# EMS_esp32_wifi_v2_4_eagle_v7.net
KiCad netlist of a schematic drawn in EAGLE
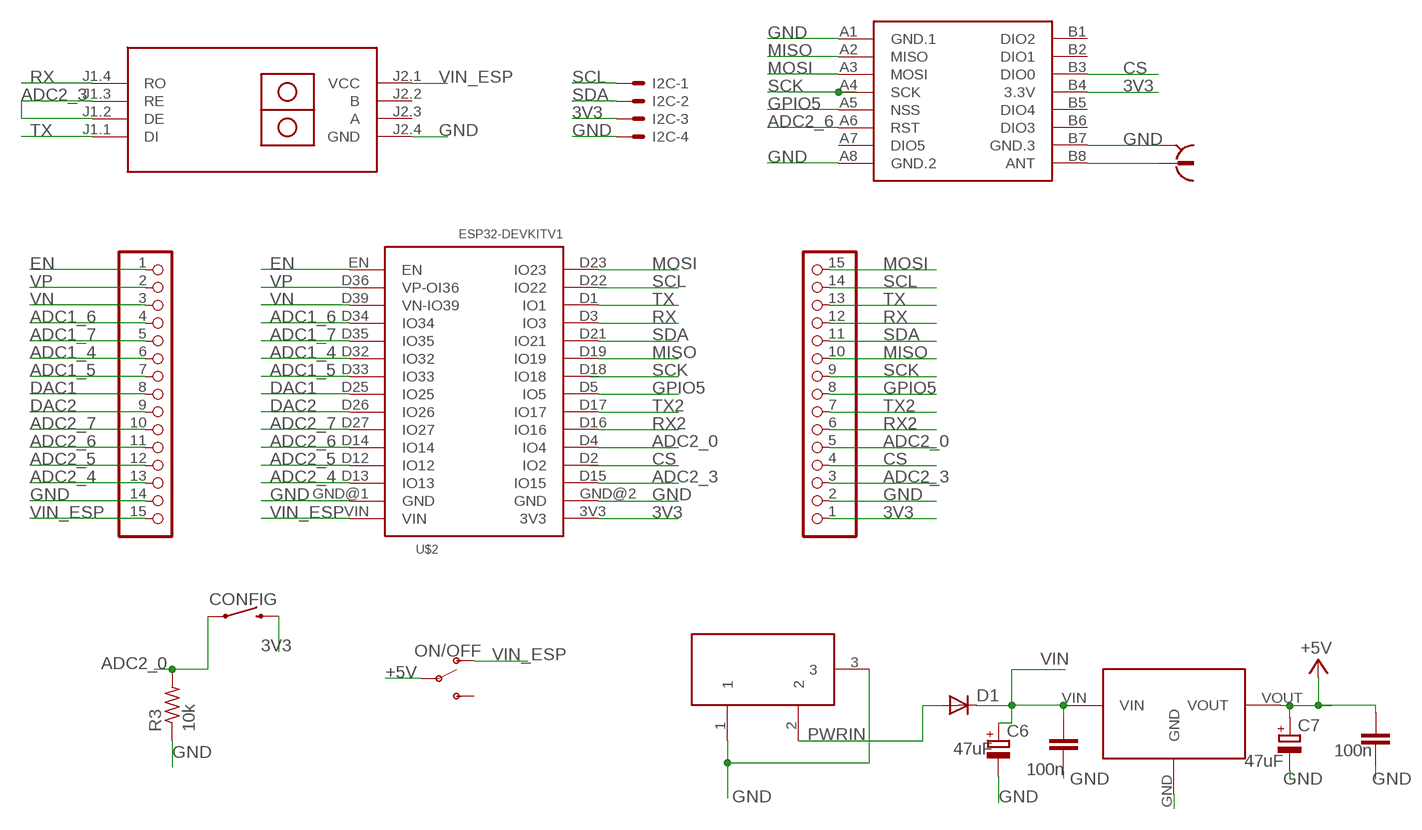
[diagram p0: schematic, sheet 1]

(export (version "E")
  (design (tool "Eeschema 10.0.6"))
  (components
    (comp (ref "C5")
      (value "100n")
      (footprint "eagle-import:C1206")
      (libsource (lib "eagle-import") (part "C-EUC1206"))
    )
    (comp (ref "C6")
      (value "47uF")
      (footprint "eagle-import:PANASONIC_D")
      (libsource (lib "eagle-import") (part "CPOL-EUD"))
    )
    (comp (ref "C7")
      (value "47uF")
      (footprint "eagle-import:PANASONIC_D")
      (libsource (lib "eagle-import") (part "CPOL-EUD"))
    )
    (comp (ref "C14")
      (value "100n")
      (footprint "eagle-import:C1206")
      (libsource (lib "eagle-import") (part "C-EUC1206"))
    )
    (comp (ref "CONFIG")
      (value "MOMENTARY-SWITCH-SPST-PTH-6.0MM")
      (footprint "eagle-import:TACTILE_SWITCH_PTH_6.0MM")
      (libsource (lib "eagle-import") (part "MOMENTARY-SWITCH-SPST-PTH-6.0MM"))
    )
    (comp (ref "D1")
      (value "DIODE-SMB")
      (footprint "eagle-import:SMB")
      (libsource (lib "eagle-import") (part "DIODE-SMB"))
    )
    (comp (ref "I2C")
      (value "22-23-2041")
      (footprint "eagle-import:22-23-2041")
      (fields (field (name "MF") "MOLEX"))
      (libsource (lib "eagle-import") (part "22-23-2041"))
    )
    (comp (ref "JP1")
      (value "PINHD-1X15")
      (footprint "eagle-import:1X15")
      (libsource (lib "eagle-import") (part "PINHD-1X15"))
    )
    (comp (ref "JP2")
      (value "PINHD-1X15")
      (footprint "eagle-import:1X15")
      (libsource (lib "eagle-import") (part "PINHD-1X15"))
    )
    (comp (ref "ON/OFF")
      (value "SWITCH-SPDT-PTH-11.6X4.0MM")
      (footprint "eagle-import:SWITCH_SPDT_PTH_11.6X4.0MM")
      (libsource (lib "eagle-import") (part "SWITCH-SPDT-PTH-11.6X4.0MM"))
    )
    (comp (ref "R3")
      (value "10k")
      (footprint "eagle-import:0204_7")
      (libsource (lib "eagle-import") (part "R-US_0204/7"))
    )
    (comp (ref "RFM95")
      (value "WIRELESS-LORA-RFM95W#SMD")
      (footprint "eagle-import:WIRELESS-LORA-RFM95W#SMD")
      (libsource (lib "eagle-import") (part "WIRELESS-LORA-RFM95W#SMD"))
    )
    (comp (ref "U$1")
      (value "RS485-TTL-CONVERTER")
      (footprint "eagle-import:RS485-TTL-CONVERTER")
      (libsource (lib "eagle-import") (part "RS485-TTL-CONVERTER"))
    )
    (comp (ref "U$2")
      (value "ESP32DEVKITV1")
      (footprint "eagle-import:ESP32-DEVKITV1")
      (libsource (lib "eagle-import") (part "ESP32DEVKITV1"))
    )
    (comp (ref "U$3")
      (value "SMARTPRJ_POWERSUPPLY_DC21MMX")
      (footprint "eagle-import:SMARTPRJ_POWERSUPPLY_DC-21MM")
      (libsource (lib "eagle-import") (part "SMARTPRJ_POWERSUPPLY_DC21MMX"))
    )
    (comp (ref "U$4")
      (value "7805-TO263_7805")
      (footprint "eagle-import:7805-TO263_TO263")
      (libsource (lib "eagle-import") (part "7805-TO263_7805"))
    )
    (comp (ref "X1")
      (value "734120110")
      (footprint "eagle-import:734120110")
      (libsource (lib "eagle-import") (part "734120110"))
    )
  )
  (nets
    (net (code "1") (name "+5V") (class "Default")
      (node (ref "C14") (pin "2") (pinfunction "2_2") (pintype "passive"))
      (node (ref "C7") (pin "+") (pinfunction "+_+") (pintype "passive"))
      (node (ref "ON/OFF") (pin "2") (pinfunction "P_2") (pintype "passive"))
      (node (ref "U$4") (pin "VOUT") (pinfunction "VOUT_VOUT") (pintype "bidirectional"))
    )
    (net (code "2") (name "/3V3") (class "Default")
      (node (ref "CONFIG") (pin "3") (pinfunction "2_3") (pintype "passive"))
      (node (ref "I2C") (pin "3") (pinfunction "S_3") (pintype "passive"))
      (node (ref "JP2") (pin "1") (pinfunction "1_1") (pintype "passive"))
      (node (ref "RFM95") (pin "B4") (pinfunction "3.3V_B4") (pintype "power_in"))
      (node (ref "U$2") (pin "3V3") (pinfunction "3V3_3V3") (pintype "bidirectional"))
    )
    (net (code "3") (name "/ADC1_4") (class "Default")
      (node (ref "JP1") (pin "6") (pinfunction "6_6") (pintype "passive"))
      (node (ref "U$2") (pin "D32") (pinfunction "IO32_D32") (pintype "bidirectional"))
    )
    (net (code "4") (name "/ADC1_5") (class "Default")
      (node (ref "JP1") (pin "7") (pinfunction "7_7") (pintype "passive"))
      (node (ref "U$2") (pin "D33") (pinfunction "IO33_D33") (pintype "bidirectional"))
    )
    (net (code "5") (name "/ADC1_6") (class "Default")
      (node (ref "JP1") (pin "4") (pinfunction "4_4") (pintype "passive"))
      (node (ref "U$2") (pin "D34") (pinfunction "IO34_D34") (pintype "bidirectional"))
    )
    (net (code "6") (name "/ADC1_7") (class "Default")
      (node (ref "JP1") (pin "5") (pinfunction "5_5") (pintype "passive"))
      (node (ref "U$2") (pin "D35") (pinfunction "IO35_D35") (pintype "bidirectional"))
    )
    (net (code "7") (name "/ADC2_0") (class "Default")
      (node (ref "CONFIG") (pin "1") (pinfunction "1_1") (pintype "passive"))
      (node (ref "JP2") (pin "5") (pinfunction "5_5") (pintype "passive"))
      (node (ref "R3") (pin "2") (pinfunction "2_2") (pintype "passive"))
      (node (ref "U$2") (pin "D4") (pinfunction "IO4_D4") (pintype "bidirectional"))
    )
    (net (code "8") (name "/ADC2_3") (class "Default")
      (node (ref "JP2") (pin "3") (pinfunction "3_3") (pintype "passive"))
      (node (ref "U$1") (pin "J1.2") (pinfunction "DE_J1.2") (pintype "passive"))
      (node (ref "U$1") (pin "J1.3") (pinfunction "RE_J1.3") (pintype "passive"))
      (node (ref "U$2") (pin "D15") (pinfunction "IO15_D15") (pintype "bidirectional"))
    )
    (net (code "9") (name "/ADC2_4") (class "Default")
      (node (ref "JP1") (pin "13") (pinfunction "13_13") (pintype "passive"))
      (node (ref "U$2") (pin "D13") (pinfunction "IO13_D13") (pintype "bidirectional"))
    )
    (net (code "10") (name "/ADC2_5") (class "Default")
      (node (ref "JP1") (pin "12") (pinfunction "12_12") (pintype "passive"))
      (node (ref "U$2") (pin "D12") (pinfunction "IO12_D12") (pintype "bidirectional"))
    )
    (net (code "11") (name "/ADC2_6") (class "Default")
      (node (ref "JP1") (pin "11") (pinfunction "11_11") (pintype "passive"))
      (node (ref "RFM95") (pin "A6") (pinfunction "RST_A6") (pintype "bidirectional"))
      (node (ref "U$2") (pin "D14") (pinfunction "IO14_D14") (pintype "bidirectional"))
    )
    (net (code "12") (name "/ADC2_7") (class "Default")
      (node (ref "JP1") (pin "10") (pinfunction "10_10") (pintype "passive"))
      (node (ref "U$2") (pin "D27") (pinfunction "IO27_D27") (pintype "bidirectional"))
    )
    (net (code "13") (name "/CS") (class "Default")
      (node (ref "JP2") (pin "4") (pinfunction "4_4") (pintype "passive"))
      (node (ref "RFM95") (pin "B3") (pinfunction "DIO0_B3") (pintype "bidirectional"))
      (node (ref "U$2") (pin "D2") (pinfunction "IO2_D2") (pintype "bidirectional"))
    )
    (net (code "14") (name "/DAC1") (class "Default")
      (node (ref "JP1") (pin "8") (pinfunction "8_8") (pintype "passive"))
      (node (ref "U$2") (pin "D25") (pinfunction "IO25_D25") (pintype "bidirectional"))
    )
    (net (code "15") (name "/DAC2") (class "Default")
      (node (ref "JP1") (pin "9") (pinfunction "9_9") (pintype "passive"))
      (node (ref "U$2") (pin "D26") (pinfunction "IO26_D26") (pintype "bidirectional"))
    )
    (net (code "16") (name "/EN") (class "Default")
      (node (ref "JP1") (pin "1") (pinfunction "1_1") (pintype "passive"))
      (node (ref "U$2") (pin "EN") (pinfunction "EN_EN") (pintype "bidirectional"))
    )
    (net (code "17") (name "/GND") (class "Default")
      (node (ref "C14") (pin "1") (pinfunction "1_1") (pintype "passive"))
      (node (ref "C5") (pin "1") (pinfunction "1_1") (pintype "passive"))
      (node (ref "C6") (pin "-") (pinfunction "-_-") (pintype "passive"))
      (node (ref "C7") (pin "-") (pinfunction "-_-") (pintype "passive"))
      (node (ref "I2C") (pin "4") (pinfunction "S_4") (pintype "passive"))
      (node (ref "JP1") (pin "14") (pinfunction "14_14") (pintype "passive"))
      (node (ref "JP2") (pin "2") (pinfunction "2_2") (pintype "passive"))
      (node (ref "R3") (pin "1") (pinfunction "1_1") (pintype "passive"))
      (node (ref "RFM95") (pin "A1") (pinfunction "GND.1_A1") (pintype "power_in"))
      (node (ref "RFM95") (pin "A8") (pinfunction "GND.2_A8") (pintype "power_in"))
      (node (ref "RFM95") (pin "B7") (pinfunction "GND.3_B7") (pintype "power_in"))
      (node (ref "U$1") (pin "J2.4") (pinfunction "GND_J2.4") (pintype "power_in"))
      (node (ref "U$2") (pin "GND@1") (pinfunction "GND_GND@1") (pintype "bidirectional"))
      (node (ref "U$2") (pin "GND@2") (pinfunction "GND_GND@2") (pintype "bidirectional"))
      (node (ref "U$3") (pin "1") (pinfunction "1_1") (pintype "power_in"))
      (node (ref "U$3") (pin "3") (pinfunction "3_3") (pintype "power_in"))
      (node (ref "U$4") (pin "GND") (pinfunction "GND_GND") (pintype "bidirectional"))
      (node (ref "X1") (pin "S@1") (pinfunction "2_S@1") (pintype "passive"))
      (node (ref "X1") (pin "S@2") (pinfunction "2_S@2") (pintype "passive"))
      (node (ref "X1") (pin "S@3") (pinfunction "2_S@3") (pintype "passive"))
    )
    (net (code "18") (name "/GPIO5") (class "Default")
      (node (ref "JP2") (pin "8") (pinfunction "8_8") (pintype "passive"))
      (node (ref "RFM95") (pin "A5") (pinfunction "NSS_A5") (pintype "bidirectional"))
      (node (ref "U$2") (pin "D5") (pinfunction "IO5_D5") (pintype "bidirectional"))
    )
    (net (code "19") (name "/MISO") (class "Default")
      (node (ref "JP2") (pin "10") (pinfunction "10_10") (pintype "passive"))
      (node (ref "RFM95") (pin "A2") (pinfunction "MISO_A2") (pintype "bidirectional"))
      (node (ref "U$2") (pin "D19") (pinfunction "IO19_D19") (pintype "bidirectional"))
    )
    (net (code "20") (name "/MOSI") (class "Default")
      (node (ref "JP2") (pin "15") (pinfunction "15_15") (pintype "passive"))
      (node (ref "RFM95") (pin "A3") (pinfunction "MOSI_A3") (pintype "bidirectional"))
      (node (ref "U$2") (pin "D23") (pinfunction "IO23_D23") (pintype "bidirectional"))
    )
    (net (code "21") (name "/PWRIN") (class "Default")
      (node (ref "D1") (pin "A") (pinfunction "A_A") (pintype "passive"))
      (node (ref "U$3") (pin "2") (pinfunction "2_2") (pintype "power_in"))
    )
    (net (code "22") (name "/RX") (class "Default")
      (node (ref "JP2") (pin "12") (pinfunction "12_12") (pintype "passive"))
      (node (ref "U$1") (pin "J1.4") (pinfunction "RO_J1.4") (pintype "passive"))
      (node (ref "U$2") (pin "D3") (pinfunction "IO3_D3") (pintype "bidirectional"))
    )
    (net (code "23") (name "/RX2") (class "Default")
      (node (ref "JP2") (pin "6") (pinfunction "6_6") (pintype "passive"))
      (node (ref "U$2") (pin "D16") (pinfunction "IO16_D16") (pintype "bidirectional"))
    )
    (net (code "24") (name "/SCK") (class "Default")
      (node (ref "JP2") (pin "9") (pinfunction "9_9") (pintype "passive"))
      (node (ref "RFM95") (pin "A4") (pinfunction "SCK_A4") (pintype "bidirectional"))
      (node (ref "U$2") (pin "D18") (pinfunction "IO18_D18") (pintype "bidirectional"))
    )
    (net (code "25") (name "/SCL") (class "Default")
      (node (ref "I2C") (pin "1") (pinfunction "S_1") (pintype "passive"))
      (node (ref "JP2") (pin "14") (pinfunction "14_14") (pintype "passive"))
      (node (ref "U$2") (pin "D22") (pinfunction "IO22_D22") (pintype "bidirectional"))
    )
    (net (code "26") (name "/SDA") (class "Default")
      (node (ref "I2C") (pin "2") (pinfunction "S_2") (pintype "passive"))
      (node (ref "JP2") (pin "11") (pinfunction "11_11") (pintype "passive"))
      (node (ref "U$2") (pin "D21") (pinfunction "IO21_D21") (pintype "bidirectional"))
    )
    (net (code "27") (name "/TX") (class "Default")
      (node (ref "JP2") (pin "13") (pinfunction "13_13") (pintype "passive"))
      (node (ref "U$1") (pin "J1.1") (pinfunction "DI_J1.1") (pintype "passive"))
      (node (ref "U$2") (pin "D1") (pinfunction "IO1_D1") (pintype "bidirectional"))
    )
    (net (code "28") (name "/TX2") (class "Default")
      (node (ref "JP2") (pin "7") (pinfunction "7_7") (pintype "passive"))
      (node (ref "U$2") (pin "D17") (pinfunction "IO17_D17") (pintype "bidirectional"))
    )
    (net (code "29") (name "/VIN") (class "Default")
      (node (ref "C5") (pin "2") (pinfunction "2_2") (pintype "passive"))
      (node (ref "C6") (pin "+") (pinfunction "+_+") (pintype "passive"))
      (node (ref "D1") (pin "C") (pinfunction "C_C") (pintype "passive"))
      (node (ref "U$4") (pin "VIN") (pinfunction "VIN_VIN") (pintype "bidirectional"))
    )
    (net (code "30") (name "/VIN_ESP") (class "Default")
      (node (ref "JP1") (pin "15") (pinfunction "15_15") (pintype "passive"))
      (node (ref "ON/OFF") (pin "1") (pinfunction "O_1") (pintype "passive"))
      (node (ref "U$1") (pin "J2.1") (pinfunction "VCC_J2.1") (pintype "power_in"))
      (node (ref "U$2") (pin "VIN") (pinfunction "VIN_VIN") (pintype "bidirectional"))
    )
    (net (code "31") (name "/VN") (class "Default")
      (node (ref "JP1") (pin "3") (pinfunction "3_3") (pintype "passive"))
      (node (ref "U$2") (pin "D39") (pinfunction "VN-IO39_D39") (pintype "bidirectional"))
    )
    (net (code "32") (name "/VP") (class "Default")
      (node (ref "JP1") (pin "2") (pinfunction "2_2") (pintype "passive"))
      (node (ref "U$2") (pin "D36") (pinfunction "VP-OI36_D36") (pintype "bidirectional"))
    )
    (net (code "33") (name "Net-(RFM95-ANT)") (class "Default")
      (node (ref "RFM95") (pin "B8") (pinfunction "ANT_B8") (pintype "passive"))
      (node (ref "X1") (pin "1") (pinfunction "1_1") (pintype "passive"))
    )
    (net (code "34") (name "unconnected-(ON/OFF-S-Pad3)") (class "Default")
      (node (ref "ON/OFF") (pin "3") (pinfunction "S_3") (pintype "passive"))
    )
    (net (code "35") (name "unconnected-(RFM95-DIO1-PadB2)") (class "Default")
      (node (ref "RFM95") (pin "B2") (pinfunction "DIO1_B2") (pintype "bidirectional"))
    )
    (net (code "36") (name "unconnected-(RFM95-DIO2-PadB1)") (class "Default")
      (node (ref "RFM95") (pin "B1") (pinfunction "DIO2_B1") (pintype "bidirectional"))
    )
    (net (code "37") (name "unconnected-(RFM95-DIO3-PadB6)") (class "Default")
      (node (ref "RFM95") (pin "B6") (pinfunction "DIO3_B6") (pintype "bidirectional"))
    )
    (net (code "38") (name "unconnected-(RFM95-DIO4-PadB5)") (class "Default")
      (node (ref "RFM95") (pin "B5") (pinfunction "DIO4_B5") (pintype "bidirectional"))
    )
    (net (code "39") (name "unconnected-(RFM95-DIO5-PadA7)") (class "Default")
      (node (ref "RFM95") (pin "A7") (pinfunction "DIO5_A7") (pintype "bidirectional"))
    )
    (net (code "40") (name "unconnected-(U$1-A-PadJ2.3)") (class "Default")
      (node (ref "U$1") (pin "J2.3") (pinfunction "A_J2.3") (pintype "passive"))
    )
    (net (code "41") (name "unconnected-(U$1-B-PadJ2.2)") (class "Default")
      (node (ref "U$1") (pin "J2.2") (pinfunction "B_J2.2") (pintype "passive"))
    )
  )
)
